# machnld.net
KiCad netlist of a schematic drawn in Altium Designer
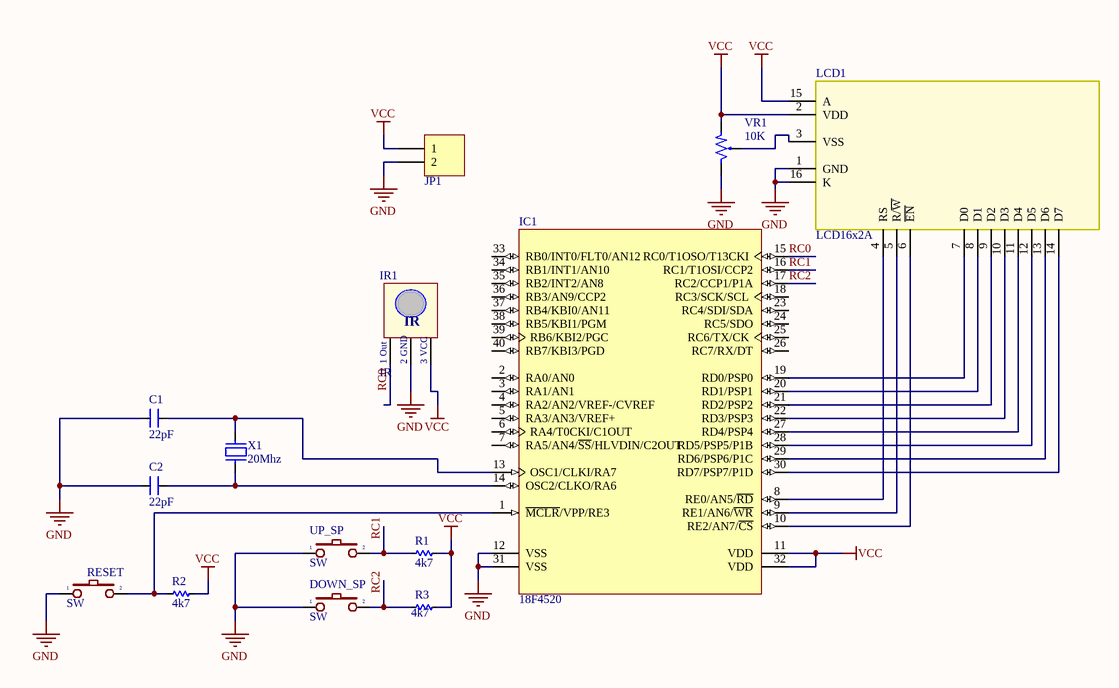
[diagram p0: machnld.SchDoc]

(export (version "E")
  (design (tool "Eeschema 10.0.6"))
  (components
    (comp (ref "C1")
      (value "22pF")
      (footprint "CN1.5")
      (description "Cap np 682pF => 104pF")
      (libsource (lib "Thuvienrieng") (part "CN1.5"))
    )
    (comp (ref "C2")
      (value "22pF")
      (footprint "CN1.5")
      (description "Cap np 682pF => 104pF")
      (libsource (lib "Thuvienrieng") (part "CN1.5"))
    )
    (comp (ref "DOWN_SP")
      (value "SW")
      (footprint "SW2")
      (description "Switch button 2 pin")
      (libsource (lib "Thuvienrieng") (part "SW2"))
    )
    (comp (ref "IC1")
      (value "18F4520")
      (footprint "DIP40/W0.6")
      (description "32KB Flash, 1536B RAM, 256B EFROM, 40-Pin PDIP")
      (fields (field (name "COPYRIGHT BY") "VanDungEvn"))
      (libsource (lib "Thuvienrieng") (part "18F4520"))
    )
    (comp (ref "IR1")
      (value "IR")
      (footprint "JP3-C1T")
      (description "Receiver Infraed IC")
      (libsource (lib "LIBRARY") (part "IR"))
    )
    (comp (ref "JP1")
      (value "Header 2_1")
      (footprint "HED2")
      (description "Header, 2-Pin")
      (fields (field (name "MANUFACTURER") "Generic Components"))
      (libsource (lib "Thuvienrieng") (part "Header 2_1"))
    )
    (comp (ref "LCD1")
      (value "LCD16x2A")
      (footprint "LCD16X2")
      (description "LCD dipslay 16 char, 2 line")
      (libsource (lib "Thuvienrieng") (part "LCD16x2"))
    )
    (comp (ref "R1")
      (value "4k7")
      (footprint "RES-1/2W")
      (description "Res")
      (fields
        (field (name "MANUFACTURER") "Generic Components")
        (field (name "PUBLISHER") "Altium Hobart Technology Centre")
      )
      (libsource (lib "LIBRARY") (part "Res"))
    )
    (comp (ref "R2")
      (value "4k7")
      (footprint "RES-1/2W")
      (description "Res")
      (fields
        (field (name "MANUFACTURER") "Generic Components")
        (field (name "PUBLISHER") "Altium Hobart Technology Centre")
      )
      (libsource (lib "LIBRARY") (part "Res"))
    )
    (comp (ref "R3")
      (value "4k7")
      (footprint "RES-1/2W")
      (description "Res")
      (fields
        (field (name "MANUFACTURER") "Generic Components")
        (field (name "PUBLISHER") "Altium Hobart Technology Centre")
      )
      (libsource (lib "LIBRARY") (part "Res"))
    )
    (comp (ref "RESET")
      (value "SW")
      (footprint "SW2")
      (description "Switch button 2 pin")
      (libsource (lib "Thuvienrieng") (part "SW2"))
    )
    (comp (ref "UP_SP")
      (value "SW")
      (footprint "SW2")
      (description "Switch button 2 pin")
      (libsource (lib "Thuvienrieng") (part "SW2"))
    )
    (comp (ref "VR1")
      (value "10K")
      (footprint "VR")
      (description "Var Resistor")
      (libsource (lib "Thuvienrieng") (part "VR1"))
    )
    (comp (ref "X1")
      (value "20Mhz")
      (footprint "XT2")
      (description "Crystal For all Crystal 2pin.")
      (libsource (lib "Thuvienrieng") (part "XT2"))
    )
  )
  (nets
    (net (code "1") (name "/RC0") (class "Default")
      (node (ref "IC1") (pin "15") (pinfunction "RC0/T1OSO/T13CKI_15") (pintype "bidirectional"))
      (node (ref "IR1") (pin "1") (pinfunction "Out_1") (pintype "passive"))
    )
    (net (code "2") (name "/RC1") (class "Default")
      (node (ref "IC1") (pin "16") (pinfunction "RC1/T1OSI/CCP2_16") (pintype "bidirectional"))
      (node (ref "R1") (pin "2") (pinfunction "2_2") (pintype "passive"))
      (node (ref "UP_SP") (pin "2") (pinfunction "2_2") (pintype "passive"))
    )
    (net (code "3") (name "/RC2") (class "Default")
      (node (ref "DOWN_SP") (pin "2") (pinfunction "2_2") (pintype "passive"))
      (node (ref "IC1") (pin "17") (pinfunction "RC2/CCP1/P1A_17") (pintype "bidirectional"))
      (node (ref "R3") (pin "2") (pinfunction "2_2") (pintype "passive"))
    )
    (net (code "4") (name "GND") (class "Default")
      (node (ref "C1") (pin "2") (pinfunction "2_2") (pintype "passive"))
      (node (ref "C2") (pin "2") (pinfunction "2_2") (pintype "passive"))
      (node (ref "DOWN_SP") (pin "1") (pinfunction "1_1") (pintype "passive"))
      (node (ref "IC1") (pin "12") (pinfunction "VSS_12") (pintype "power_in"))
      (node (ref "IC1") (pin "31") (pinfunction "VSS_31") (pintype "power_in"))
      (node (ref "IR1") (pin "2") (pinfunction "GND_2") (pintype "passive"))
      (node (ref "JP1") (pin "2") (pinfunction "2_2") (pintype "passive"))
      (node (ref "LCD1") (pin "1") (pinfunction "GND_1") (pintype "passive"))
      (node (ref "LCD1") (pin "16") (pinfunction "K_16") (pintype "passive"))
      (node (ref "RESET") (pin "1") (pinfunction "1_1") (pintype "passive"))
      (node (ref "UP_SP") (pin "1") (pinfunction "1_1") (pintype "passive"))
      (node (ref "VR1") (pin "3") (pinfunction "3_3") (pintype "passive"))
    )
    (net (code "5") (name "Net-(IC1-OSC1{slash}CLKI{slash}RA7)") (class "Default")
      (node (ref "C1") (pin "1") (pinfunction "1_1") (pintype "passive"))
      (node (ref "IC1") (pin "13") (pinfunction "OSC1/CLKI/RA7_13") (pintype "input"))
      (node (ref "X1") (pin "2") (pinfunction "2_2") (pintype "passive"))
    )
    (net (code "6") (name "Net-(IC1-OSC2{slash}CLKO{slash}RA6)") (class "Default")
      (node (ref "C2") (pin "1") (pinfunction "1_1") (pintype "passive"))
      (node (ref "IC1") (pin "14") (pinfunction "OSC2/CLKO/RA6_14") (pintype "bidirectional"))
      (node (ref "X1") (pin "1") (pinfunction "1_1") (pintype "passive"))
    )
    (net (code "7") (name "Net-(IC1-RD0{slash}PSP0)") (class "Default")
      (node (ref "IC1") (pin "19") (pinfunction "RD0/PSP0_19") (pintype "bidirectional"))
      (node (ref "LCD1") (pin "7") (pinfunction "D0_7") (pintype "passive"))
    )
    (net (code "8") (name "Net-(IC1-RD1{slash}PSP1)") (class "Default")
      (node (ref "IC1") (pin "20") (pinfunction "RD1/PSP1_20") (pintype "bidirectional"))
      (node (ref "LCD1") (pin "8") (pinfunction "D1_8") (pintype "passive"))
    )
    (net (code "9") (name "Net-(IC1-RD2{slash}PSP2)") (class "Default")
      (node (ref "IC1") (pin "21") (pinfunction "RD2/PSP2_21") (pintype "bidirectional"))
      (node (ref "LCD1") (pin "9") (pinfunction "D2_9") (pintype "passive"))
    )
    (net (code "10") (name "Net-(IC1-RD3{slash}PSP3)") (class "Default")
      (node (ref "IC1") (pin "22") (pinfunction "RD3/PSP3_22") (pintype "bidirectional"))
      (node (ref "LCD1") (pin "10") (pinfunction "D3_10") (pintype "passive"))
    )
    (net (code "11") (name "Net-(IC1-RD4{slash}PSP4)") (class "Default")
      (node (ref "IC1") (pin "27") (pinfunction "RD4/PSP4_27") (pintype "bidirectional"))
      (node (ref "LCD1") (pin "11") (pinfunction "D4_11") (pintype "passive"))
    )
    (net (code "12") (name "Net-(IC1-RD5{slash}PSP5{slash}P1B)") (class "Default")
      (node (ref "IC1") (pin "28") (pinfunction "RD5/PSP5/P1B_28") (pintype "bidirectional"))
      (node (ref "LCD1") (pin "12") (pinfunction "D5_12") (pintype "passive"))
    )
    (net (code "13") (name "Net-(IC1-RD6{slash}PSP6{slash}P1C)") (class "Default")
      (node (ref "IC1") (pin "29") (pinfunction "RD6/PSP6/P1C_29") (pintype "bidirectional"))
      (node (ref "LCD1") (pin "13") (pinfunction "D6_13") (pintype "passive"))
    )
    (net (code "14") (name "Net-(IC1-RD7{slash}PSP7{slash}P1D)") (class "Default")
      (node (ref "IC1") (pin "30") (pinfunction "RD7/PSP7/P1D_30") (pintype "bidirectional"))
      (node (ref "LCD1") (pin "14") (pinfunction "D7_14") (pintype "passive"))
    )
    (net (code "15") (name "Net-(IC1-RE0{slash}AN5{slash}~{RD})") (class "Default")
      (node (ref "IC1") (pin "8") (pinfunction "RE0/AN5/~{RD}_8") (pintype "bidirectional"))
      (node (ref "LCD1") (pin "4") (pinfunction "RS_4") (pintype "passive"))
    )
    (net (code "16") (name "Net-(IC1-RE1{slash}AN6{slash}~{WR})") (class "Default")
      (node (ref "IC1") (pin "9") (pinfunction "RE1/AN6/~{WR}_9") (pintype "bidirectional"))
      (node (ref "LCD1") (pin "5") (pinfunction "R/~{W}_5") (pintype "passive"))
    )
    (net (code "17") (name "Net-(IC1-RE2{slash}AN7{slash}~{CS})") (class "Default")
      (node (ref "IC1") (pin "10") (pinfunction "RE2/AN7/~{CS}_10") (pintype "bidirectional"))
      (node (ref "LCD1") (pin "6") (pinfunction "~{EN}_6") (pintype "passive"))
    )
    (net (code "18") (name "Net-(IC1-~{MCLR}{slash}VPP{slash}RE3)") (class "Default")
      (node (ref "IC1") (pin "1") (pinfunction "~{MCLR}/VPP/RE3_1") (pintype "input"))
      (node (ref "R2") (pin "2") (pinfunction "2_2") (pintype "passive"))
      (node (ref "RESET") (pin "2") (pinfunction "2_2") (pintype "passive"))
    )
    (net (code "19") (name "Net-(LCD1-VSS)") (class "Default")
      (node (ref "LCD1") (pin "3") (pinfunction "VSS_3") (pintype "passive"))
      (node (ref "VR1") (pin "2") (pinfunction "2_2") (pintype "passive"))
    )
    (net (code "20") (name "VCC") (class "Default")
      (node (ref "IC1") (pin "11") (pinfunction "VDD_11") (pintype "power_in"))
      (node (ref "IC1") (pin "32") (pinfunction "VDD_32") (pintype "power_in"))
      (node (ref "IR1") (pin "3") (pinfunction "VCC_3") (pintype "passive"))
      (node (ref "JP1") (pin "1") (pinfunction "1_1") (pintype "passive"))
      (node (ref "LCD1") (pin "15") (pinfunction "A_15") (pintype "passive"))
      (node (ref "LCD1") (pin "2") (pinfunction "VDD_2") (pintype "passive"))
      (node (ref "R1") (pin "1") (pinfunction "1_1") (pintype "passive"))
      (node (ref "R2") (pin "1") (pinfunction "1_1") (pintype "passive"))
      (node (ref "R3") (pin "1") (pinfunction "1_1") (pintype "passive"))
      (node (ref "VR1") (pin "1") (pinfunction "1_1") (pintype "passive"))
    )
    (net (code "21") (name "unconnected-(IC1-RA0{slash}AN0-Pad2)") (class "Default")
      (node (ref "IC1") (pin "2") (pinfunction "RA0/AN0_2") (pintype "bidirectional"))
    )
    (net (code "22") (name "unconnected-(IC1-RA1{slash}AN1-Pad3)") (class "Default")
      (node (ref "IC1") (pin "3") (pinfunction "RA1/AN1_3") (pintype "bidirectional"))
    )
    (net (code "23") (name "unconnected-(IC1-RA2{slash}AN2{slash}VREF-{slash}CVREF-Pad4)") (class "Default")
      (node (ref "IC1") (pin "4") (pinfunction "RA2/AN2/VREF-/CVREF_4") (pintype "bidirectional"))
    )
    (net (code "24") (name "unconnected-(IC1-RA3{slash}AN3{slash}VREF+-Pad5)") (class "Default")
      (node (ref "IC1") (pin "5") (pinfunction "RA3/AN3/VREF+_5") (pintype "bidirectional"))
    )
    (net (code "25") (name "unconnected-(IC1-RA4{slash}T0CKI{slash}C1OUT-Pad6)") (class "Default")
      (node (ref "IC1") (pin "6") (pinfunction "RA4/T0CKI/C1OUT_6") (pintype "bidirectional"))
    )
    (net (code "26") (name "unconnected-(IC1-RA5{slash}AN4{slash}~{SS}{slash}HLVDIN{slash}C2OUT-Pad7)") (class "Default")
      (node (ref "IC1") (pin "7") (pinfunction "RA5/AN4/~{SS}/HLVDIN/C2OUT_7") (pintype "bidirectional"))
    )
    (net (code "27") (name "unconnected-(IC1-RB0{slash}INT0{slash}FLT0{slash}AN12-Pad33)") (class "Default")
      (node (ref "IC1") (pin "33") (pinfunction "RB0/INT0/FLT0/AN12_33") (pintype "bidirectional"))
    )
    (net (code "28") (name "unconnected-(IC1-RB1{slash}INT1{slash}AN10-Pad34)") (class "Default")
      (node (ref "IC1") (pin "34") (pinfunction "RB1/INT1/AN10_34") (pintype "bidirectional"))
    )
    (net (code "29") (name "unconnected-(IC1-RB2{slash}INT2{slash}AN8-Pad35)") (class "Default")
      (node (ref "IC1") (pin "35") (pinfunction "RB2/INT2/AN8_35") (pintype "bidirectional"))
    )
    (net (code "30") (name "unconnected-(IC1-RB3{slash}AN9{slash}CCP2-Pad36)") (class "Default")
      (node (ref "IC1") (pin "36") (pinfunction "RB3/AN9/CCP2_36") (pintype "bidirectional"))
    )
    (net (code "31") (name "unconnected-(IC1-RB4{slash}KBI0{slash}AN11-Pad37)") (class "Default")
      (node (ref "IC1") (pin "37") (pinfunction "RB4/KBI0/AN11_37") (pintype "bidirectional"))
    )
    (net (code "32") (name "unconnected-(IC1-RB5{slash}KBI1{slash}PGM-Pad38)") (class "Default")
      (node (ref "IC1") (pin "38") (pinfunction "RB5/KBI1/PGM_38") (pintype "bidirectional"))
    )
    (net (code "33") (name "unconnected-(IC1-RB6{slash}KBI2{slash}PGC-Pad39)") (class "Default")
      (node (ref "IC1") (pin "39") (pinfunction "RB6/KBI2/PGC_39") (pintype "bidirectional"))
    )
    (net (code "34") (name "unconnected-(IC1-RB7{slash}KBI3{slash}PGD-Pad40)") (class "Default")
      (node (ref "IC1") (pin "40") (pinfunction "RB7/KBI3/PGD_40") (pintype "bidirectional"))
    )
    (net (code "35") (name "unconnected-(IC1-RC3{slash}SCK{slash}SCL-Pad18)") (class "Default")
      (node (ref "IC1") (pin "18") (pinfunction "RC3/SCK/SCL_18") (pintype "bidirectional"))
    )
    (net (code "36") (name "unconnected-(IC1-RC4{slash}SDI{slash}SDA-Pad23)") (class "Default")
      (node (ref "IC1") (pin "23") (pinfunction "RC4/SDI/SDA_23") (pintype "bidirectional"))
    )
    (net (code "37") (name "unconnected-(IC1-RC5{slash}SDO-Pad24)") (class "Default")
      (node (ref "IC1") (pin "24") (pinfunction "RC5/SDO_24") (pintype "bidirectional"))
    )
    (net (code "38") (name "unconnected-(IC1-RC6{slash}TX{slash}CK-Pad25)") (class "Default")
      (node (ref "IC1") (pin "25") (pinfunction "RC6/TX/CK_25") (pintype "bidirectional"))
    )
    (net (code "39") (name "unconnected-(IC1-RC7{slash}RX{slash}DT-Pad26)") (class "Default")
      (node (ref "IC1") (pin "26") (pinfunction "RC7/RX/DT_26") (pintype "bidirectional"))
    )
  )
)
